# SCH_Teensy-PWM-Machine_2025-12-06.net
KiCad netlist of a schematic drawn in EasyEDA
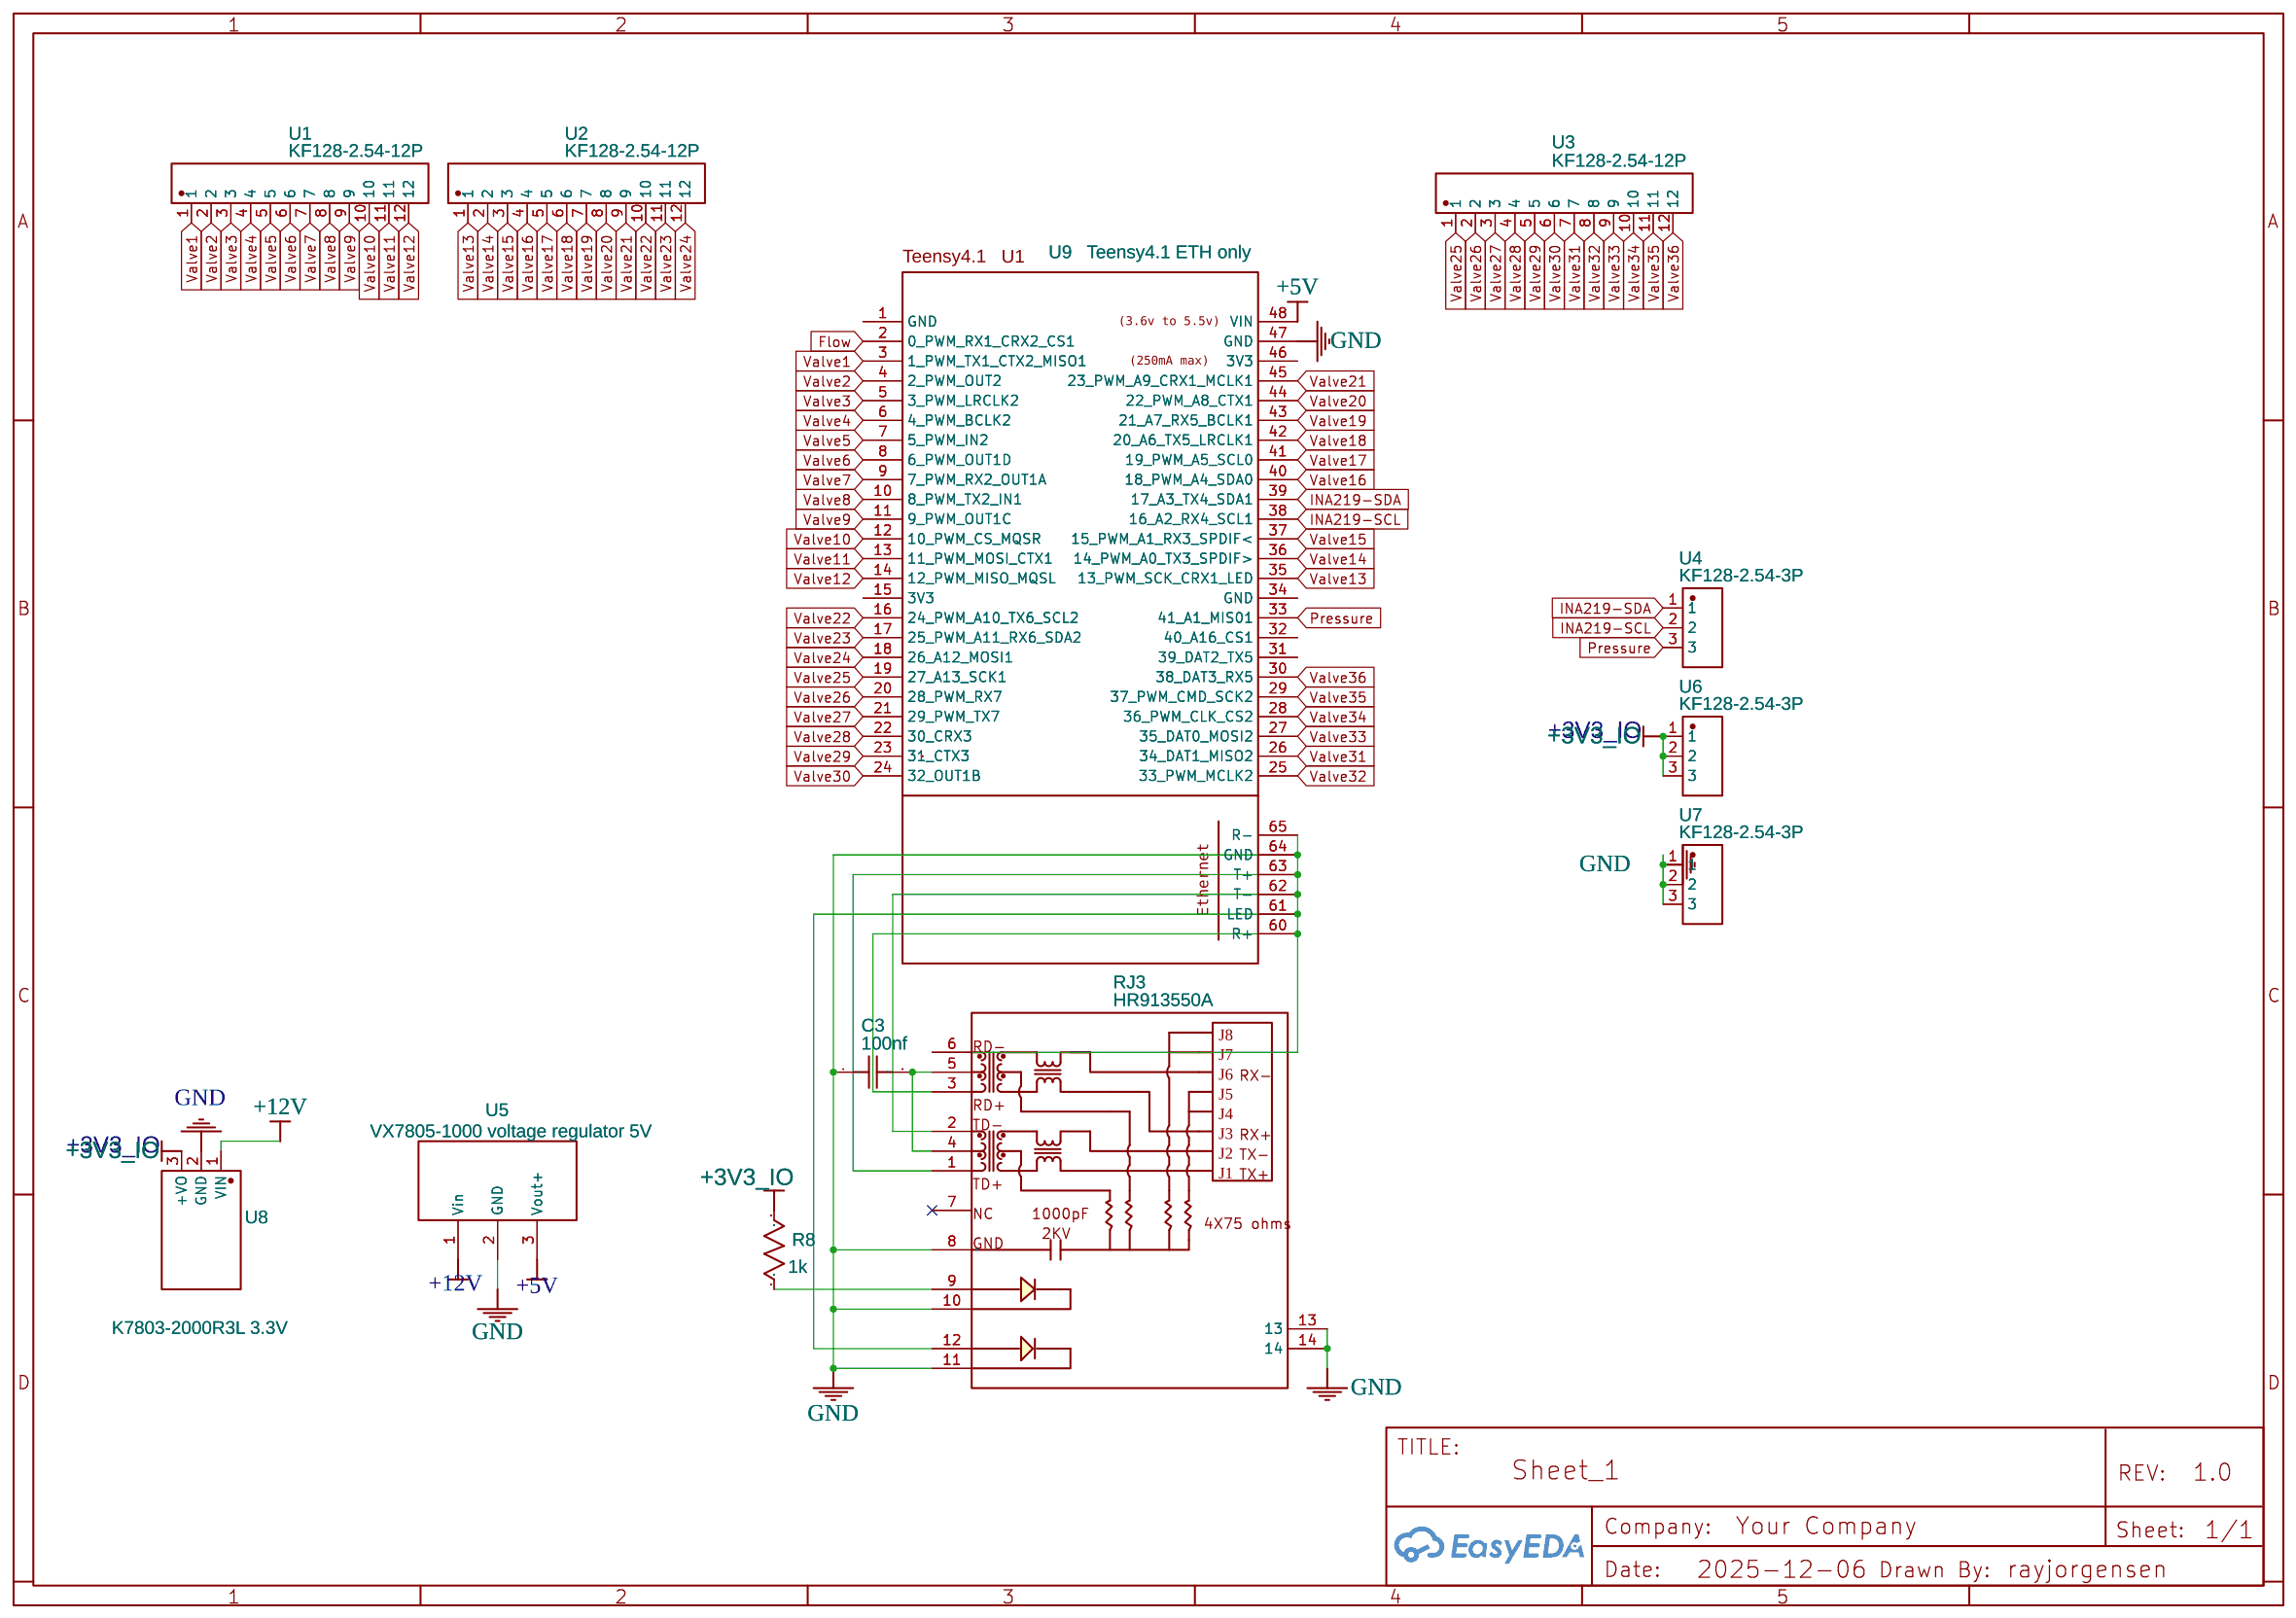
[diagram p0: schematic sheet]

(export (version "E")
  (design (tool "Eeschema 10.0.6"))
  (components
    (comp (ref "C3") (value "100nf") (libsource (lib "") (part "C_RAD-0.1_US")))
    (comp (ref "R8") (value "1k") (libsource (lib "") (part "R_AXIAL-0.4_US")))
    (comp (ref "RJ3")
      (value "HR913550A")
      (fields (field (name "Manufacturer") "HANRUN"))
      (libsource (lib "") (part "HR913550A"))
    )
    (comp (ref "U1")
      (value "KF128-2.54-12P")
      (fields (field (name "Manufacturer") "KEFA(科发)"))
      (libsource (lib "") (part "KF128-2.54-12P"))
    )
    (comp (ref "U2")
      (value "KF128-2.54-12P")
      (fields (field (name "Manufacturer") "KEFA(科发)"))
      (libsource (lib "") (part "KF128-2.54-12P"))
    )
    (comp (ref "U3")
      (value "KF128-2.54-12P")
      (fields (field (name "Manufacturer") "KEFA(科发)"))
      (libsource (lib "") (part "KF128-2.54-12P"))
    )
    (comp (ref "U4")
      (value "KF128-2.54-3P")
      (fields (field (name "Manufacturer") "KEFA(科发)"))
      (libsource (lib "") (part "KF128-2.54-3P"))
    )
    (comp (ref "U5")
      (value "VX7805-1000 voltage regulator 5V")
      (fields (field (name "Manufacturer Part") "VX7805-1000") (field (name "Manufacturer") "CUI"))
      (libsource (lib "") (part "VX7805-1000 voltage regulator"))
    )
    (comp (ref "U6")
      (value "KF128-2.54-3P")
      (fields (field (name "Manufacturer") "KEFA(科发)"))
      (libsource (lib "") (part "KF128-2.54-3P"))
    )
    (comp (ref "U7")
      (value "KF128-2.54-3P")
      (fields (field (name "Manufacturer") "KEFA(科发)"))
      (libsource (lib "") (part "KF128-2.54-3P"))
    )
    (comp (ref "U8")
      (value "K7803-2000R3L 3.3V")
      (fields
        (field (name "Manufacturer Part") "K7803-2000")
        (field (name "Manufacturer") "MORNSUN Guangzhou S& T")
      )
      (libsource (lib "") (part "K7803-2000R3L"))
    )
    (comp (ref "U9")
      (value "Teensy4.1 ETH only")
      (fields (field (name "Manufacturer Part") "Teensy4.1") (field (name "Manufacturer") "PJRC"))
      (libsource (lib "") (part "Teensy4.1 ETH only"))
    )
  )
  (nets
    (net (code "1") (name "+3V3_IO") (class "Default")
      (node (ref "R8") (pin "2") (pinfunction "2_2") (pintype "unspecified"))
      (node (ref "U6") (pin "1") (pinfunction "1_1") (pintype "unspecified"))
      (node (ref "U6") (pin "2") (pinfunction "2_2") (pintype "unspecified"))
      (node (ref "U6") (pin "3") (pinfunction "3_3") (pintype "unspecified"))
      (node (ref "U8") (pin "3") (pinfunction "+VO_3") (pintype "unspecified"))
    )
    (net (code "2") (name "+5V") (class "Default")
      (node (ref "U5") (pin "3") (pinfunction "Vout+_3") (pintype "unspecified"))
      (node (ref "U9") (pin "48") (pinfunction "VIN_48") (pintype "bidirectional"))
    )
    (net (code "3") (name "+12V") (class "Default")
      (node (ref "U5") (pin "1") (pinfunction "Vin_1") (pintype "unspecified"))
      (node (ref "U8") (pin "1") (pinfunction "VIN_1") (pintype "unspecified"))
    )
    (net (code "4") (name "Flow") (class "Default")
      (node (ref "U9") (pin "2") (pinfunction "0_PWM_RX1_CRX2_CS1_2") (pintype "bidirectional"))
    )
    (net (code "5") (name "GND") (class "Default")
      (node (ref "C3") (pin "1") (pinfunction "1_1") (pintype "unspecified"))
      (node (ref "RJ3") (pin "1") (pintype "unspecified"))
      (node (ref "RJ3") (pin "10") (pintype "unspecified"))
      (node (ref "RJ3") (pin "11") (pintype "unspecified"))
      (node (ref "RJ3") (pin "12") (pintype "unspecified"))
      (node (ref "RJ3") (pin "13") (pinfunction "13_13") (pintype "unspecified"))
      (node (ref "RJ3") (pin "14") (pinfunction "14_14") (pintype "unspecified"))
      (node (ref "RJ3") (pin "2") (pintype "unspecified"))
      (node (ref "RJ3") (pin "3") (pintype "unspecified"))
      (node (ref "RJ3") (pin "6") (pintype "unspecified"))
      (node (ref "RJ3") (pin "8") (pinfunction "GND_8") (pintype "unspecified"))
      (node (ref "U5") (pin "2") (pinfunction "GND_2") (pintype "unspecified"))
      (node (ref "U7") (pin "1") (pinfunction "1_1") (pintype "unspecified"))
      (node (ref "U7") (pin "2") (pinfunction "2_2") (pintype "unspecified"))
      (node (ref "U7") (pin "3") (pinfunction "3_3") (pintype "unspecified"))
      (node (ref "U8") (pin "2") (pinfunction "GND_2") (pintype "unspecified"))
      (node (ref "U9") (pin "47") (pinfunction "GND_47") (pintype "bidirectional"))
      (node (ref "U9") (pin "60") (pinfunction "R+_60") (pintype "bidirectional"))
      (node (ref "U9") (pin "61") (pinfunction "LED_61") (pintype "bidirectional"))
      (node (ref "U9") (pin "62") (pinfunction "T-_62") (pintype "bidirectional"))
      (node (ref "U9") (pin "63") (pinfunction "T+_63") (pintype "bidirectional"))
      (node (ref "U9") (pin "64") (pinfunction "GND_64") (pintype "bidirectional"))
      (node (ref "U9") (pin "65") (pinfunction "R-_65") (pintype "bidirectional"))
    )
    (net (code "6") (name "INA219-SCL") (class "Default")
      (node (ref "U4") (pin "2") (pinfunction "2_2") (pintype "unspecified"))
      (node (ref "U9") (pin "38") (pinfunction "16_A2_RX4_SCL1_38") (pintype "bidirectional"))
    )
    (net (code "7") (name "INA219-SDA") (class "Default")
      (node (ref "U4") (pin "1") (pinfunction "1_1") (pintype "unspecified"))
      (node (ref "U9") (pin "39") (pinfunction "17_A3_TX4_SDA1_39") (pintype "bidirectional"))
    )
    (net (code "8") (name "Net-(C3-Pad2)") (class "Default")
      (node (ref "C3") (pin "2") (pinfunction "2_2") (pintype "unspecified"))
      (node (ref "RJ3") (pin "4") (pintype "unspecified"))
      (node (ref "RJ3") (pin "5") (pintype "unspecified"))
    )
    (net (code "9") (name "Net-(R8-Pad1)") (class "Default")
      (node (ref "R8") (pin "1") (pinfunction "1_1") (pintype "unspecified"))
      (node (ref "RJ3") (pin "9") (pintype "unspecified"))
    )
    (net (code "10") (name "Pressure") (class "Default")
      (node (ref "U4") (pin "3") (pinfunction "3_3") (pintype "unspecified"))
      (node (ref "U9") (pin "33") (pinfunction "41_A1_MIS01_33") (pintype "bidirectional"))
    )
    (net (code "11") (name "Valve1") (class "Default")
      (node (ref "U1") (pin "1") (pinfunction "1_1") (pintype "unspecified"))
      (node (ref "U9") (pin "3") (pinfunction "1_PWM_TX1_CTX2_MISO1_3") (pintype "bidirectional"))
    )
    (net (code "12") (name "Valve2") (class "Default")
      (node (ref "U1") (pin "2") (pinfunction "2_2") (pintype "unspecified"))
      (node (ref "U9") (pin "4") (pinfunction "2_PWM_OUT2_4") (pintype "bidirectional"))
    )
    (net (code "13") (name "Valve3") (class "Default")
      (node (ref "U1") (pin "3") (pinfunction "3_3") (pintype "unspecified"))
      (node (ref "U9") (pin "5") (pinfunction "3_PWM_LRCLK2_5") (pintype "bidirectional"))
    )
    (net (code "14") (name "Valve4") (class "Default")
      (node (ref "U1") (pin "4") (pinfunction "4_4") (pintype "unspecified"))
      (node (ref "U9") (pin "6") (pinfunction "4_PWM_BCLK2_6") (pintype "bidirectional"))
    )
    (net (code "15") (name "Valve5") (class "Default")
      (node (ref "U1") (pin "5") (pinfunction "5_5") (pintype "unspecified"))
      (node (ref "U9") (pin "7") (pinfunction "5_PWM_IN2_7") (pintype "bidirectional"))
    )
    (net (code "16") (name "Valve6") (class "Default")
      (node (ref "U1") (pin "6") (pinfunction "6_6") (pintype "unspecified"))
      (node (ref "U9") (pin "8") (pinfunction "6_PWM_OUT1D_8") (pintype "bidirectional"))
    )
    (net (code "17") (name "Valve7") (class "Default")
      (node (ref "U1") (pin "7") (pinfunction "7_7") (pintype "unspecified"))
      (node (ref "U9") (pin "9") (pinfunction "7_PWM_RX2_OUT1A_9") (pintype "bidirectional"))
    )
    (net (code "18") (name "Valve8") (class "Default")
      (node (ref "U1") (pin "8") (pinfunction "8_8") (pintype "unspecified"))
      (node (ref "U9") (pin "10") (pinfunction "8_PWM_TX2_IN1_10") (pintype "bidirectional"))
    )
    (net (code "19") (name "Valve9") (class "Default")
      (node (ref "U1") (pin "9") (pinfunction "9_9") (pintype "unspecified"))
      (node (ref "U9") (pin "11") (pinfunction "9_PWM_OUT1C_11") (pintype "bidirectional"))
    )
    (net (code "20") (name "Valve10") (class "Default")
      (node (ref "U1") (pin "10") (pinfunction "10_10") (pintype "unspecified"))
      (node (ref "U9") (pin "12") (pinfunction "10_PWM_CS_MQSR_12") (pintype "bidirectional"))
    )
    (net (code "21") (name "Valve11") (class "Default")
      (node (ref "U1") (pin "11") (pinfunction "11_11") (pintype "unspecified"))
      (node (ref "U9") (pin "13") (pinfunction "11_PWM_MOSI_CTX1_13") (pintype "bidirectional"))
    )
    (net (code "22") (name "Valve12") (class "Default")
      (node (ref "U1") (pin "12") (pinfunction "12_12") (pintype "unspecified"))
      (node (ref "U9") (pin "14") (pinfunction "12_PWM_MISO_MQSL_14") (pintype "bidirectional"))
    )
    (net (code "23") (name "Valve13") (class "Default")
      (node (ref "U2") (pin "1") (pinfunction "1_1") (pintype "unspecified"))
      (node (ref "U9") (pin "35") (pinfunction "13_PWM_SCK_CRX1_LED_35") (pintype "bidirectional"))
    )
    (net (code "24") (name "Valve14") (class "Default")
      (node (ref "U2") (pin "2") (pinfunction "2_2") (pintype "unspecified"))
      (node (ref "U9") (pin "36") (pinfunction "14_PWM_A0_TX3_SPDIF>_36") (pintype "bidirectional"))
    )
    (net (code "25") (name "Valve15") (class "Default")
      (node (ref "U2") (pin "3") (pinfunction "3_3") (pintype "unspecified"))
      (node (ref "U9") (pin "37") (pinfunction "15_PWM_A1_RX3_SPDIF<_37") (pintype "bidirectional"))
    )
    (net (code "26") (name "Valve16") (class "Default")
      (node (ref "U2") (pin "4") (pinfunction "4_4") (pintype "unspecified"))
      (node (ref "U9") (pin "40") (pinfunction "18_PWM_A4_SDA0_40") (pintype "bidirectional"))
    )
    (net (code "27") (name "Valve17") (class "Default")
      (node (ref "U2") (pin "5") (pinfunction "5_5") (pintype "unspecified"))
      (node (ref "U9") (pin "41") (pinfunction "19_PWM_A5_SCL0_41") (pintype "bidirectional"))
    )
    (net (code "28") (name "Valve18") (class "Default")
      (node (ref "U2") (pin "6") (pinfunction "6_6") (pintype "unspecified"))
      (node (ref "U9") (pin "42") (pinfunction "20_A6_TX5_LRCLK1_42") (pintype "bidirectional"))
    )
    (net (code "29") (name "Valve19") (class "Default")
      (node (ref "U2") (pin "7") (pinfunction "7_7") (pintype "unspecified"))
      (node (ref "U9") (pin "43") (pinfunction "21_A7_RX5_BCLK1_43") (pintype "bidirectional"))
    )
    (net (code "30") (name "Valve20") (class "Default")
      (node (ref "U2") (pin "8") (pinfunction "8_8") (pintype "unspecified"))
      (node (ref "U9") (pin "44") (pinfunction "22_PWM_A8_CTX1_44") (pintype "bidirectional"))
    )
    (net (code "31") (name "Valve21") (class "Default")
      (node (ref "U2") (pin "9") (pinfunction "9_9") (pintype "unspecified"))
      (node (ref "U9") (pin "45") (pinfunction "23_PWM_A9_CRX1_MCLK1_45") (pintype "bidirectional"))
    )
    (net (code "32") (name "Valve22") (class "Default")
      (node (ref "U2") (pin "10") (pinfunction "10_10") (pintype "unspecified"))
      (node (ref "U9") (pin "16") (pinfunction "24_PWM_A10_TX6_SCL2_16") (pintype "bidirectional"))
    )
    (net (code "33") (name "Valve23") (class "Default")
      (node (ref "U2") (pin "11") (pinfunction "11_11") (pintype "unspecified"))
      (node (ref "U9") (pin "17") (pinfunction "25_PWM_A11_RX6_SDA2_17") (pintype "bidirectional"))
    )
    (net (code "34") (name "Valve24") (class "Default")
      (node (ref "U2") (pin "12") (pinfunction "12_12") (pintype "unspecified"))
      (node (ref "U9") (pin "18") (pinfunction "26_A12_MOSI1_18") (pintype "bidirectional"))
    )
    (net (code "35") (name "Valve25") (class "Default")
      (node (ref "U3") (pin "1") (pinfunction "1_1") (pintype "unspecified"))
      (node (ref "U9") (pin "19") (pinfunction "27_A13_SCK1_19") (pintype "bidirectional"))
    )
    (net (code "36") (name "Valve26") (class "Default")
      (node (ref "U3") (pin "2") (pinfunction "2_2") (pintype "unspecified"))
      (node (ref "U9") (pin "20") (pinfunction "28_PWM_RX7_20") (pintype "bidirectional"))
    )
    (net (code "37") (name "Valve27") (class "Default")
      (node (ref "U3") (pin "3") (pinfunction "3_3") (pintype "unspecified"))
      (node (ref "U9") (pin "21") (pinfunction "29_PWM_TX7_21") (pintype "bidirectional"))
    )
    (net (code "38") (name "Valve28") (class "Default")
      (node (ref "U3") (pin "4") (pinfunction "4_4") (pintype "unspecified"))
      (node (ref "U9") (pin "22") (pinfunction "30_CRX3_22") (pintype "bidirectional"))
    )
    (net (code "39") (name "Valve29") (class "Default")
      (node (ref "U3") (pin "5") (pinfunction "5_5") (pintype "unspecified"))
      (node (ref "U9") (pin "23") (pinfunction "31_CTX3_23") (pintype "bidirectional"))
    )
    (net (code "40") (name "Valve30") (class "Default")
      (node (ref "U3") (pin "6") (pinfunction "6_6") (pintype "unspecified"))
      (node (ref "U9") (pin "24") (pinfunction "32_OUT1B_24") (pintype "bidirectional"))
    )
    (net (code "41") (name "Valve31") (class "Default")
      (node (ref "U3") (pin "7") (pinfunction "7_7") (pintype "unspecified"))
      (node (ref "U9") (pin "26") (pinfunction "34_DAT1_MISO2_26") (pintype "bidirectional"))
    )
    (net (code "42") (name "Valve32") (class "Default")
      (node (ref "U3") (pin "8") (pinfunction "8_8") (pintype "unspecified"))
      (node (ref "U9") (pin "25") (pinfunction "33_PWM_MCLK2_25") (pintype "bidirectional"))
    )
    (net (code "43") (name "Valve33") (class "Default")
      (node (ref "U3") (pin "9") (pinfunction "9_9") (pintype "unspecified"))
      (node (ref "U9") (pin "27") (pinfunction "35_DAT0_MOSI2_27") (pintype "bidirectional"))
    )
    (net (code "44") (name "Valve34") (class "Default")
      (node (ref "U3") (pin "10") (pinfunction "10_10") (pintype "unspecified"))
      (node (ref "U9") (pin "28") (pinfunction "36_PWM_CLK_CS2_28") (pintype "bidirectional"))
    )
    (net (code "45") (name "Valve35") (class "Default")
      (node (ref "U3") (pin "11") (pinfunction "11_11") (pintype "unspecified"))
      (node (ref "U9") (pin "29") (pinfunction "37_PWM_CMD_SCK2_29") (pintype "bidirectional"))
    )
    (net (code "46") (name "Valve36") (class "Default")
      (node (ref "U3") (pin "12") (pinfunction "12_12") (pintype "unspecified"))
      (node (ref "U9") (pin "30") (pinfunction "38_DAT3_RX5_30") (pintype "bidirectional"))
    )
    (net (code "47") (name "unconnected-(RJ3-NC-Pad7)") (class "Default")
      (node (ref "RJ3") (pin "7") (pinfunction "NC_7") (pintype "unspecified+no_connect"))
    )
    (net (code "48") (name "unconnected-(U9-3V3-Pad15)") (class "Default")
      (node (ref "U9") (pin "15") (pinfunction "3V3_15") (pintype "bidirectional"))
    )
    (net (code "49") (name "unconnected-(U9-3V3-Pad46)") (class "Default")
      (node (ref "U9") (pin "46") (pinfunction "3V3_46") (pintype "bidirectional"))
    )
    (net (code "50") (name "unconnected-(U9-39_DAT2_TX5-Pad31)") (class "Default")
      (node (ref "U9") (pin "31") (pinfunction "39_DAT2_TX5_31") (pintype "bidirectional"))
    )
    (net (code "51") (name "unconnected-(U9-40_A16_CS1-Pad32)") (class "Default")
      (node (ref "U9") (pin "32") (pinfunction "40_A16_CS1_32") (pintype "bidirectional"))
    )
    (net (code "52") (name "unconnected-(U9-GND-Pad1)") (class "Default")
      (node (ref "U9") (pin "1") (pinfunction "GND_1") (pintype "bidirectional"))
    )
    (net (code "53") (name "unconnected-(U9-GND-Pad34)") (class "Default")
      (node (ref "U9") (pin "34") (pinfunction "GND_34") (pintype "bidirectional"))
    )
  )
)
